# Power_Supply_2.net
KiCad netlist of a schematic drawn in EAGLE
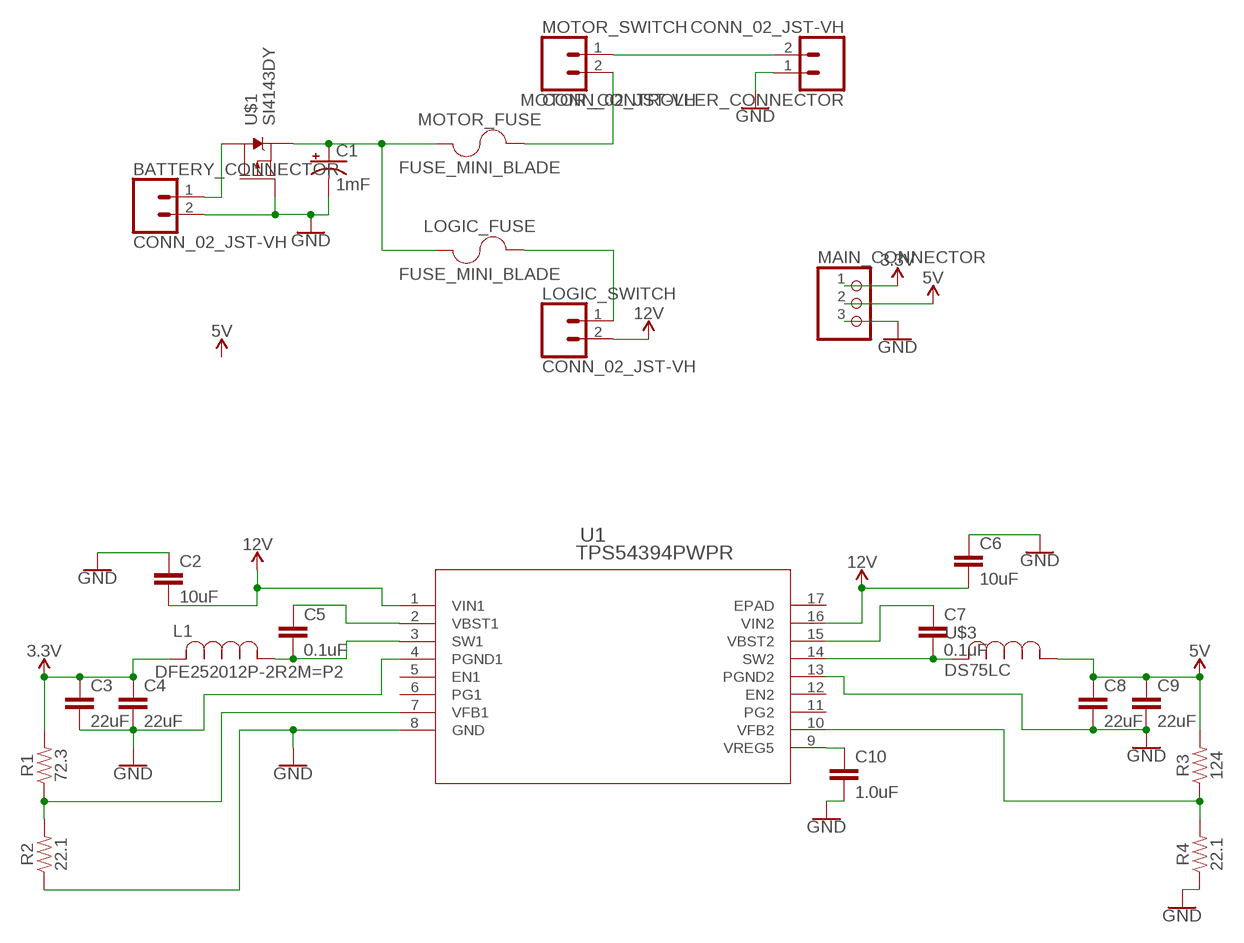
[diagram p0: schematic, sheet 1]

(export (version "E")
  (design (tool "Eeschema 10.0.6"))
  (components
    (comp (ref "BATTERY_CONNECTOR")
      (value "CONN_02_JST-VH")
      (footprint "eagle-import:B2P-VH")
      (libsource (lib "eagle-import") (part "CONN_02_JST-VH"))
    )
    (comp (ref "C1")
      (value "1mF")
      (footprint "eagle-import:CPOL-RADIAL-5MM-10MM")
      (libsource (lib "eagle-import") (part "1000UF-RADIAL-5MM-25V-20%"))
    )
    (comp (ref "C2")
      (value "10uF")
      (footprint "eagle-import:0805")
      (libsource (lib "eagle-import") (part "10UF-0805-10V-10%"))
    )
    (comp (ref "C3")
      (value "22uF")
      (footprint "eagle-import:0805")
      (libsource (lib "eagle-import") (part "22UF-0805-6.3V-20%"))
    )
    (comp (ref "C4")
      (value "22uF")
      (footprint "eagle-import:0805")
      (libsource (lib "eagle-import") (part "22UF-0805-6.3V-20%"))
    )
    (comp (ref "C5")
      (value "0.1uF")
      (footprint "eagle-import:0603")
      (libsource (lib "eagle-import") (part "0.1UF-0603-25V-5%"))
    )
    (comp (ref "C6")
      (value "10uF")
      (footprint "eagle-import:0805")
      (libsource (lib "eagle-import") (part "10UF-0805-10V-10%"))
    )
    (comp (ref "C7")
      (value "0.1uF")
      (footprint "eagle-import:0603")
      (libsource (lib "eagle-import") (part "0.1UF-0603-25V-5%"))
    )
    (comp (ref "C8")
      (value "22uF")
      (footprint "eagle-import:0805")
      (libsource (lib "eagle-import") (part "22UF-0805-6.3V-20%"))
    )
    (comp (ref "C9")
      (value "22uF")
      (footprint "eagle-import:0805")
      (libsource (lib "eagle-import") (part "22UF-0805-6.3V-20%"))
    )
    (comp (ref "C10")
      (value "1.0uF")
      (footprint "eagle-import:0805")
      (libsource (lib "eagle-import") (part "1.0UF-0805-25V-10%"))
    )
    (comp (ref "L1")
      (value "DFE252012P-2R2M=P2")
      (footprint "eagle-import:DFE252012P-1R0M=P2")
      (fields (field (name "MANUFACTURER_PART_NUMBER") "DFE252012P2R2M=P2"))
      (libsource (lib "eagle-import") (part "DFE252012P-2R2M=P2"))
    )
    (comp (ref "LOGIC_FUSE")
      (value "FUSE_MINI_BLADE")
      (footprint "eagle-import:SL-1538")
      (libsource (lib "eagle-import") (part "FUSE_MINI_BLADE"))
    )
    (comp (ref "LOGIC_SWITCH")
      (value "CONN_02_JST-VH")
      (footprint "eagle-import:B2P-VH")
      (libsource (lib "eagle-import") (part "CONN_02_JST-VH"))
    )
    (comp (ref "MAIN_CONNECTOR")
      (value "PINHD-1X3")
      (footprint "eagle-import:1X03")
      (libsource (lib "eagle-import") (part "PINHD-1X3"))
    )
    (comp (ref "MOTOR_CONTROLLER_CONNECTOR")
      (value "CONN_02_JST-VH")
      (footprint "eagle-import:B2P-VH")
      (libsource (lib "eagle-import") (part "CONN_02_JST-VH"))
    )
    (comp (ref "MOTOR_FUSE")
      (value "FUSE_MINI_BLADE")
      (footprint "eagle-import:SL-1538")
      (libsource (lib "eagle-import") (part "FUSE_MINI_BLADE"))
    )
    (comp (ref "MOTOR_SWITCH")
      (value "CONN_02_JST-VH")
      (footprint "eagle-import:B2P-VH")
      (libsource (lib "eagle-import") (part "CONN_02_JST-VH"))
    )
    (comp (ref "R1")
      (value "72.3")
      (footprint "eagle-import:0603")
      (libsource (lib "eagle-import") (part "75KOHM-0603-1/10W-1%"))
    )
    (comp (ref "R2")
      (value "22.1")
      (footprint "eagle-import:0603")
      (libsource (lib "eagle-import") (part "75KOHM-0603-1/10W-1%"))
    )
    (comp (ref "R3")
      (value "124")
      (footprint "eagle-import:0603")
      (libsource (lib "eagle-import") (part "75KOHM-0603-1/10W-1%"))
    )
    (comp (ref "R4")
      (value "22.1")
      (footprint "eagle-import:0603")
      (libsource (lib "eagle-import") (part "75KOHM-0603-1/10W-1%"))
    )
    (comp (ref "U$1")
      (value "SI4143DY")
      (footprint "eagle-import:SO-8")
      (libsource (lib "eagle-import") (part "SI4143DY"))
    )
    (comp (ref "U$3")
      (value "DS75LC")
      (footprint "eagle-import:DS75LC")
      (libsource (lib "eagle-import") (part "DS75LC"))
    )
    (comp (ref "U1")
      (value "TPS54394PWPR")
      (footprint "eagle-import:PWP16_3P4X2P46")
      (libsource (lib "eagle-import") (part "TPS54394PWPR"))
    )
  )
  (nets
    (net (code "1") (name "3.3V") (class "Default")
      (node (ref "C3") (pin "1") (pinfunction "1_1") (pintype "passive"))
      (node (ref "C4") (pin "1") (pinfunction "1_1") (pintype "passive"))
      (node (ref "L1") (pin "2") (pinfunction "2_2") (pintype "passive"))
      (node (ref "MAIN_CONNECTOR") (pin "1") (pinfunction "1_1") (pintype "passive"))
      (node (ref "R1") (pin "2") (pinfunction "2_2") (pintype "passive"))
    )
    (net (code "2") (name "5V") (class "Default")
      (node (ref "C8") (pin "1") (pinfunction "1_1") (pintype "passive"))
      (node (ref "C9") (pin "1") (pinfunction "1_1") (pintype "passive"))
      (node (ref "MAIN_CONNECTOR") (pin "2") (pinfunction "2_2") (pintype "passive"))
      (node (ref "R3") (pin "2") (pinfunction "2_2") (pintype "passive"))
      (node (ref "U$3") (pin "P$1") (pinfunction "1_P$1") (pintype "passive"))
    )
    (net (code "3") (name "12V") (class "Default")
      (node (ref "C2") (pin "2") (pinfunction "2_2") (pintype "passive"))
      (node (ref "C6") (pin "2") (pinfunction "2_2") (pintype "passive"))
      (node (ref "LOGIC_SWITCH") (pin "2") (pinfunction "2_2") (pintype "passive"))
      (node (ref "U1") (pin "1") (pinfunction "VIN1_1") (pintype "input"))
      (node (ref "U1") (pin "16") (pinfunction "VIN2_16") (pintype "input"))
    )
    (net (code "4") (name "GND") (class "Default")
      (node (ref "BATTERY_CONNECTOR") (pin "2") (pinfunction "2_2") (pintype "passive"))
      (node (ref "C1") (pin "-") (pinfunction "-_-") (pintype "passive"))
      (node (ref "C10") (pin "2") (pinfunction "2_2") (pintype "passive"))
      (node (ref "C2") (pin "1") (pinfunction "1_1") (pintype "passive"))
      (node (ref "C3") (pin "2") (pinfunction "2_2") (pintype "passive"))
      (node (ref "C4") (pin "2") (pinfunction "2_2") (pintype "passive"))
      (node (ref "C6") (pin "1") (pinfunction "1_1") (pintype "passive"))
      (node (ref "C8") (pin "2") (pinfunction "2_2") (pintype "passive"))
      (node (ref "C9") (pin "2") (pinfunction "2_2") (pintype "passive"))
      (node (ref "MAIN_CONNECTOR") (pin "3") (pinfunction "3_3") (pintype "passive"))
      (node (ref "MOTOR_CONTROLLER_CONNECTOR") (pin "1") (pinfunction "1_1") (pintype "passive"))
      (node (ref "R2") (pin "1") (pinfunction "1_1") (pintype "passive"))
      (node (ref "R4") (pin "1") (pinfunction "1_1") (pintype "passive"))
      (node (ref "U$1") (pin "4") (pinfunction "G_4") (pintype "bidirectional"))
      (node (ref "U1") (pin "13") (pinfunction "PGND2_13") (pintype "bidirectional"))
      (node (ref "U1") (pin "4") (pinfunction "PGND1_4") (pintype "power_in"))
      (node (ref "U1") (pin "8") (pinfunction "GND_8") (pintype "bidirectional"))
    )
    (net (code "5") (name "Net-(BATTERY_CONNECTOR-Pad1)") (class "Default")
      (node (ref "BATTERY_CONNECTOR") (pin "1") (pinfunction "1_1") (pintype "passive"))
      (node (ref "U$1") (pin "5") (pinfunction "D_5") (pintype "bidirectional"))
      (node (ref "U$1") (pin "6") (pinfunction "D_6") (pintype "bidirectional"))
      (node (ref "U$1") (pin "7") (pinfunction "D_7") (pintype "bidirectional"))
      (node (ref "U$1") (pin "8") (pinfunction "D_8") (pintype "bidirectional"))
    )
    (net (code "6") (name "Net-(LOGIC_FUSE-1)") (class "Default")
      (node (ref "C1") (pin "+") (pinfunction "+_+") (pintype "passive"))
      (node (ref "LOGIC_FUSE") (pin "P$1") (pinfunction "1_P$1") (pintype "bidirectional"))
      (node (ref "MOTOR_FUSE") (pin "P$1") (pinfunction "1_P$1") (pintype "bidirectional"))
      (node (ref "U$1") (pin "1") (pinfunction "S_1") (pintype "bidirectional"))
      (node (ref "U$1") (pin "2") (pinfunction "S_2") (pintype "bidirectional"))
      (node (ref "U$1") (pin "3") (pinfunction "S_3") (pintype "bidirectional"))
    )
    (net (code "7") (name "Net-(LOGIC_FUSE-2)") (class "Default")
      (node (ref "LOGIC_FUSE") (pin "P$2") (pinfunction "2_P$2") (pintype "bidirectional"))
      (node (ref "LOGIC_SWITCH") (pin "1") (pinfunction "1_1") (pintype "passive"))
    )
    (net (code "8") (name "Net-(MOTOR_CONTROLLER_CONNECTOR-Pad2)") (class "Default")
      (node (ref "MOTOR_CONTROLLER_CONNECTOR") (pin "2") (pinfunction "2_2") (pintype "passive"))
      (node (ref "MOTOR_SWITCH") (pin "1") (pinfunction "1_1") (pintype "passive"))
    )
    (net (code "9") (name "Net-(MOTOR_FUSE-2)") (class "Default")
      (node (ref "MOTOR_FUSE") (pin "P$2") (pinfunction "2_P$2") (pintype "bidirectional"))
      (node (ref "MOTOR_SWITCH") (pin "2") (pinfunction "2_2") (pintype "passive"))
    )
    (net (code "10") (name "Net-(U$3-2)") (class "Default")
      (node (ref "C7") (pin "2") (pinfunction "2_2") (pintype "passive"))
      (node (ref "U$3") (pin "P$2") (pinfunction "2_P$2") (pintype "passive"))
      (node (ref "U1") (pin "14") (pinfunction "SW2_14") (pintype "bidirectional"))
    )
    (net (code "11") (name "Net-(U1-SW1)") (class "Default")
      (node (ref "C5") (pin "2") (pinfunction "2_2") (pintype "passive"))
      (node (ref "L1") (pin "1") (pinfunction "1_1") (pintype "passive"))
      (node (ref "U1") (pin "3") (pinfunction "SW1_3") (pintype "bidirectional"))
    )
    (net (code "12") (name "Net-(U1-VBST1)") (class "Default")
      (node (ref "C5") (pin "1") (pinfunction "1_1") (pintype "passive"))
      (node (ref "U1") (pin "2") (pinfunction "VBST1_2") (pintype "input"))
    )
    (net (code "13") (name "Net-(U1-VBST2)") (class "Default")
      (node (ref "C7") (pin "1") (pinfunction "1_1") (pintype "passive"))
      (node (ref "U1") (pin "15") (pinfunction "VBST2_15") (pintype "input"))
    )
    (net (code "14") (name "Net-(U1-VFB1)") (class "Default")
      (node (ref "R1") (pin "1") (pinfunction "1_1") (pintype "passive"))
      (node (ref "R2") (pin "2") (pinfunction "2_2") (pintype "passive"))
      (node (ref "U1") (pin "7") (pinfunction "VFB1_7") (pintype "input"))
    )
    (net (code "15") (name "Net-(U1-VFB2)") (class "Default")
      (node (ref "R3") (pin "1") (pinfunction "1_1") (pintype "passive"))
      (node (ref "R4") (pin "2") (pinfunction "2_2") (pintype "passive"))
      (node (ref "U1") (pin "10") (pinfunction "VFB2_10") (pintype "input"))
    )
    (net (code "16") (name "Net-(U1-VREG5)") (class "Default")
      (node (ref "C10") (pin "1") (pinfunction "1_1") (pintype "passive"))
      (node (ref "U1") (pin "9") (pinfunction "VREG5_9") (pintype "output"))
    )
    (net (code "17") (name "unconnected-(U1-EN1-Pad5)") (class "Default")
      (node (ref "U1") (pin "5") (pinfunction "EN1_5") (pintype "input"))
    )
    (net (code "18") (name "unconnected-(U1-EN2-Pad12)") (class "Default")
      (node (ref "U1") (pin "12") (pinfunction "EN2_12") (pintype "input"))
    )
    (net (code "19") (name "unconnected-(U1-EPAD-Pad17)") (class "Default")
      (node (ref "U1") (pin "17") (pinfunction "EPAD_17") (pintype "passive"))
    )
    (net (code "20") (name "unconnected-(U1-PG1-Pad6)") (class "Default")
      (node (ref "U1") (pin "6") (pinfunction "PG1_6") (pintype "output"))
    )
    (net (code "21") (name "unconnected-(U1-PG2-Pad11)") (class "Default")
      (node (ref "U1") (pin "11") (pinfunction "PG2_11") (pintype "output"))
    )
  )
)
